# temp-sensor.net
KiCad netlist of a schematic drawn in EAGLE
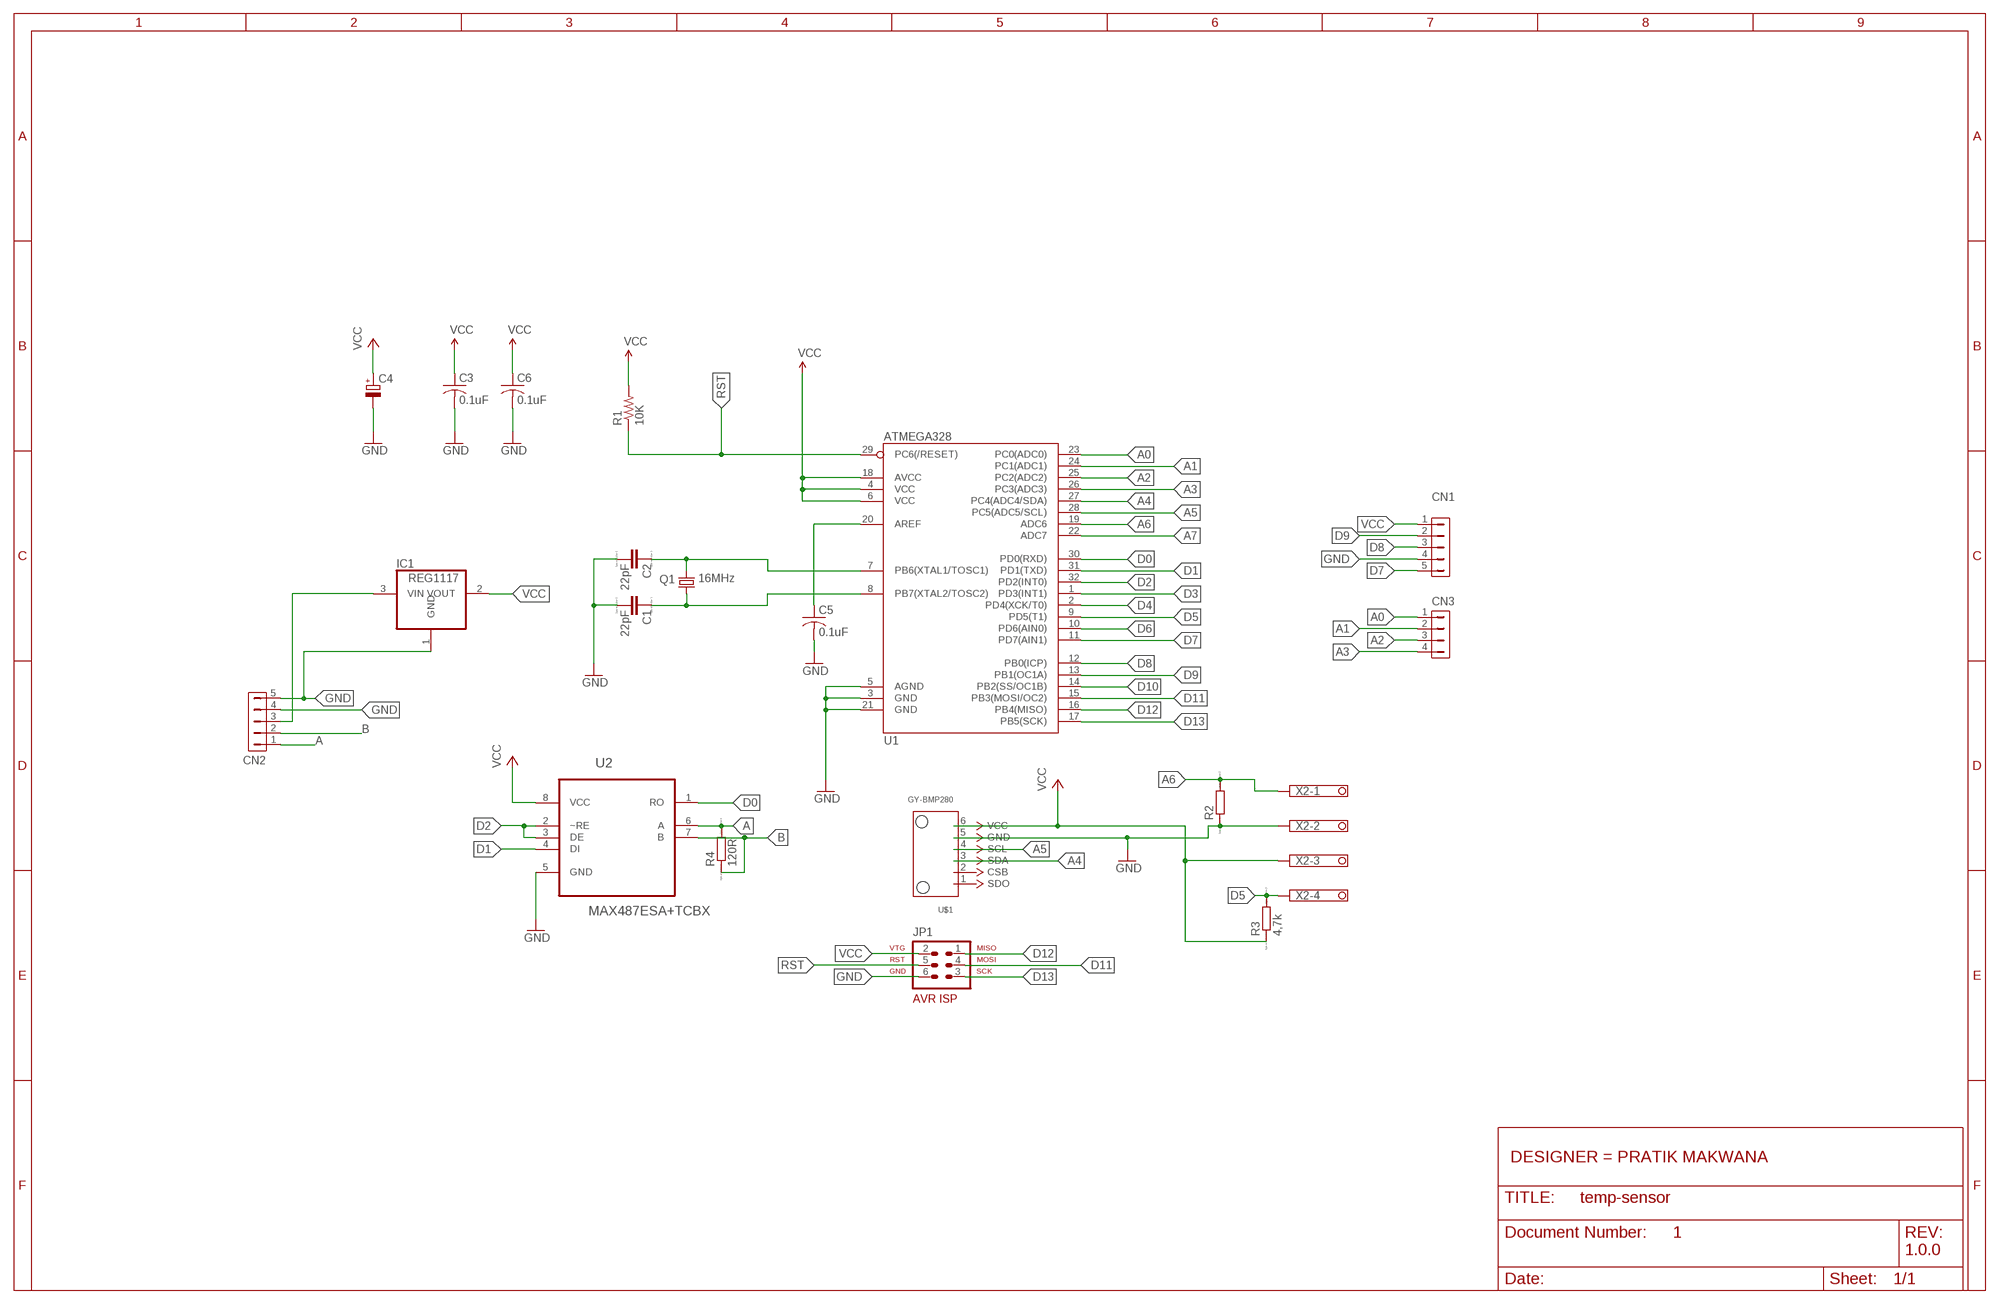
[diagram p0: schematic, sheet 1]

(export (version "E")
  (design (tool "Eeschema 10.0.6"))
  (components
    (comp (ref "C1")
      (value "22pF")
      (footprint "eagle-import:C0805")
      (libsource (lib "eagle-import") (part "C"))
    )
    (comp (ref "C2")
      (value "22pF")
      (footprint "eagle-import:C0805")
      (libsource (lib "eagle-import") (part "C"))
    )
    (comp (ref "C3")
      (value "0.1uF")
      (footprint "eagle-import:C0805")
      (libsource (lib "eagle-import") (part "C-USC0805"))
    )
    (comp (ref "C4")
      (value "CPOL-EUSANYO_SMD_C6")
      (footprint "eagle-import:SANYO-OSCON_SMD_C6")
      (libsource (lib "eagle-import") (part "CPOL-EUSANYO_SMD_C6"))
    )
    (comp (ref "C5")
      (value "0.1uF")
      (footprint "eagle-import:C0805")
      (libsource (lib "eagle-import") (part "C-USC0805"))
    )
    (comp (ref "C6")
      (value "0.1uF")
      (footprint "eagle-import:C0805")
      (libsource (lib "eagle-import") (part "C-USC0805"))
    )
    (comp (ref "CN1")
      (value "HDR-1X5-SIP-100")
      (footprint "eagle-import:SIP-100-5V")
      (libsource (lib "eagle-import") (part "HDR-1X5-SIP-100"))
    )
    (comp (ref "CN2")
      (value "HDR-1X5-SIP-100")
      (footprint "eagle-import:SIP-100-5V")
      (libsource (lib "eagle-import") (part "HDR-1X5-SIP-100"))
    )
    (comp (ref "CN3")
      (value "HDR-1X4-SIP-100")
      (footprint "eagle-import:SIP-100-4V")
      (libsource (lib "eagle-import") (part "HDR-1X4-SIP-100"))
    )
    (comp (ref "IC1")
      (value "REG1117")
      (footprint "eagle-import:SOT223")
      (libsource (lib "eagle-import") (part "REG1117"))
    )
    (comp (ref "JP1")
      (value "AVR-ISP-6")
      (footprint "eagle-import:AVR-ISP-6")
      (libsource (lib "eagle-import") (part "AVR-ISP-6"))
    )
    (comp (ref "Q1")
      (value "16MHz")
      (footprint "eagle-import:HC49_S")
      (libsource (lib "eagle-import") (part "CRYTALHC49S"))
    )
    (comp (ref "R1")
      (value "10K")
      (footprint "eagle-import:R1206")
      (libsource (lib "eagle-import") (part "R-US_R1206"))
    )
    (comp (ref "R2")
      (value "RR1206")
      (footprint "eagle-import:R1206")
      (libsource (lib "eagle-import") (part "RR1206"))
    )
    (comp (ref "R3")
      (value "4,7k")
      (footprint "eagle-import:R1206")
      (libsource (lib "eagle-import") (part "RR1206"))
    )
    (comp (ref "R4")
      (value "120R")
      (footprint "eagle-import:R0603")
      (libsource (lib "eagle-import") (part "RR0603"))
    )
    (comp (ref "U$1")
      (value "GY-BMP280")
      (footprint "eagle-import:GY-BMP280")
      (libsource (lib "eagle-import") (part "GY-BMP280"))
    )
    (comp (ref "U1")
      (value "ATMEGA328")
      (footprint "eagle-import:TQFP32-08")
      (libsource (lib "eagle-import") (part "ATMEGA328"))
    )
    (comp (ref "U2")
      (value "MAX487ESA+TCBX")
      (footprint "eagle-import:SOIC127P600X175-8N")
      (fields (field (name "MF") "Maxim Integrated"))
      (libsource (lib "eagle-import") (part "MAX487ESA+TCBX"))
    )
    (comp (ref "X2")
      (value "TERMINAL-BLOCK-3.5MM-4-PIN-LONG-PAD")
      (footprint "eagle-import:TERMINAL-BLOCK-4-PIN-3.5MM-LONG-PAD")
      (libsource (lib "eagle-import") (part "TERMINAL-BLOCK-3.5MM-4-PIN-LONG-PAD"))
    )
  )
  (nets
    (net (code "1") (name "A") (class "Default")
      (node (ref "CN2") (pin "1") (pinfunction "1_1") (pintype "passive"))
      (node (ref "R4") (pin "2") (pinfunction "2_2") (pintype "passive"))
      (node (ref "U2") (pin "6") (pinfunction "A_6") (pintype "bidirectional"))
    )
    (net (code "2") (name "A0") (class "Default")
      (node (ref "CN3") (pin "1") (pinfunction "1_1") (pintype "passive"))
      (node (ref "U1") (pin "23") (pinfunction "PC0(ADC0)_23") (pintype "bidirectional"))
    )
    (net (code "3") (name "A1") (class "Default")
      (node (ref "CN3") (pin "2") (pinfunction "2_2") (pintype "passive"))
      (node (ref "U1") (pin "24") (pinfunction "PC1(ADC1)_24") (pintype "bidirectional"))
    )
    (net (code "4") (name "A2") (class "Default")
      (node (ref "CN3") (pin "3") (pinfunction "3_3") (pintype "passive"))
      (node (ref "U1") (pin "25") (pinfunction "PC2(ADC2)_25") (pintype "bidirectional"))
    )
    (net (code "5") (name "A3") (class "Default")
      (node (ref "CN3") (pin "4") (pinfunction "4_4") (pintype "passive"))
      (node (ref "U1") (pin "26") (pinfunction "PC3(ADC3)_26") (pintype "bidirectional"))
    )
    (net (code "6") (name "A4") (class "Default")
      (node (ref "U$1") (pin "3") (pinfunction "SDA_3") (pintype "bidirectional"))
      (node (ref "U1") (pin "27") (pinfunction "PC4(ADC4/SDA)_27") (pintype "bidirectional"))
    )
    (net (code "7") (name "A5") (class "Default")
      (node (ref "U$1") (pin "4") (pinfunction "SCL_4") (pintype "bidirectional"))
      (node (ref "U1") (pin "28") (pinfunction "PC5(ADC5/SCL)_28") (pintype "bidirectional"))
    )
    (net (code "8") (name "A6") (class "Default")
      (node (ref "R2") (pin "2") (pinfunction "2_2") (pintype "passive"))
      (node (ref "U1") (pin "19") (pinfunction "ADC6_19") (pintype "bidirectional"))
      (node (ref "X2") (pin "1") (pinfunction "K_1") (pintype "passive"))
    )
    (net (code "9") (name "A7") (class "Default")
      (node (ref "U1") (pin "22") (pinfunction "ADC7_22") (pintype "bidirectional"))
    )
    (net (code "10") (name "B") (class "Default")
      (node (ref "CN2") (pin "2") (pinfunction "2_2") (pintype "passive"))
      (node (ref "R4") (pin "1") (pinfunction "1_1") (pintype "passive"))
      (node (ref "U2") (pin "7") (pinfunction "B_7") (pintype "bidirectional"))
    )
    (net (code "11") (name "D0") (class "Default")
      (node (ref "U1") (pin "30") (pinfunction "PD0(RXD)_30") (pintype "bidirectional"))
      (node (ref "U2") (pin "1") (pinfunction "RO_1") (pintype "output"))
    )
    (net (code "12") (name "D1") (class "Default")
      (node (ref "U1") (pin "31") (pinfunction "PD1(TXD)_31") (pintype "bidirectional"))
      (node (ref "U2") (pin "4") (pinfunction "DI_4") (pintype "input"))
    )
    (net (code "13") (name "D2") (class "Default")
      (node (ref "U1") (pin "32") (pinfunction "PD2(INT0)_32") (pintype "bidirectional"))
      (node (ref "U2") (pin "2") (pinfunction "~{RE}_2") (pintype "input"))
      (node (ref "U2") (pin "3") (pinfunction "DE_3") (pintype "input"))
    )
    (net (code "14") (name "D3") (class "Default")
      (node (ref "U1") (pin "1") (pinfunction "PD3(INT1)_1") (pintype "bidirectional"))
    )
    (net (code "15") (name "D4") (class "Default")
      (node (ref "U1") (pin "2") (pinfunction "PD4(XCK/T0)_2") (pintype "bidirectional"))
    )
    (net (code "16") (name "D5") (class "Default")
      (node (ref "R3") (pin "2") (pinfunction "2_2") (pintype "passive"))
      (node (ref "U1") (pin "9") (pinfunction "PD5(T1)_9") (pintype "bidirectional"))
      (node (ref "X2") (pin "4") (pinfunction "K_4") (pintype "passive"))
    )
    (net (code "17") (name "D6") (class "Default")
      (node (ref "U1") (pin "10") (pinfunction "PD6(AIN0)_10") (pintype "bidirectional"))
    )
    (net (code "18") (name "D7") (class "Default")
      (node (ref "CN1") (pin "5") (pinfunction "5_5") (pintype "passive"))
      (node (ref "U1") (pin "11") (pinfunction "PD7(AIN1)_11") (pintype "bidirectional"))
    )
    (net (code "19") (name "D8") (class "Default")
      (node (ref "CN1") (pin "3") (pinfunction "3_3") (pintype "passive"))
      (node (ref "U1") (pin "12") (pinfunction "PB0(ICP)_12") (pintype "bidirectional"))
    )
    (net (code "20") (name "D9") (class "Default")
      (node (ref "CN1") (pin "2") (pinfunction "2_2") (pintype "passive"))
      (node (ref "U1") (pin "13") (pinfunction "PB1(OC1A)_13") (pintype "bidirectional"))
    )
    (net (code "21") (name "D10") (class "Default")
      (node (ref "U1") (pin "14") (pinfunction "PB2(SS/OC1B)_14") (pintype "bidirectional"))
    )
    (net (code "22") (name "D11") (class "Default")
      (node (ref "JP1") (pin "4") (pinfunction "4_4") (pintype "passive"))
      (node (ref "U1") (pin "15") (pinfunction "PB3(MOSI/OC2)_15") (pintype "bidirectional"))
    )
    (net (code "23") (name "D12") (class "Default")
      (node (ref "JP1") (pin "1") (pinfunction "1_1") (pintype "passive"))
      (node (ref "U1") (pin "16") (pinfunction "PB4(MISO)_16") (pintype "bidirectional"))
    )
    (net (code "24") (name "D13") (class "Default")
      (node (ref "JP1") (pin "3") (pinfunction "3_3") (pintype "passive"))
      (node (ref "U1") (pin "17") (pinfunction "PB5(SCK)_17") (pintype "bidirectional"))
    )
    (net (code "25") (name "GND") (class "Default")
      (node (ref "C1") (pin "2") (pinfunction "2_2") (pintype "passive"))
      (node (ref "C2") (pin "2") (pinfunction "2_2") (pintype "passive"))
      (node (ref "C3") (pin "2") (pinfunction "2_2") (pintype "passive"))
      (node (ref "C4") (pin "-") (pinfunction "-_-") (pintype "passive"))
      (node (ref "C5") (pin "2") (pinfunction "2_2") (pintype "passive"))
      (node (ref "C6") (pin "2") (pinfunction "2_2") (pintype "passive"))
      (node (ref "CN1") (pin "4") (pinfunction "4_4") (pintype "passive"))
      (node (ref "CN2") (pin "4") (pinfunction "4_4") (pintype "passive"))
      (node (ref "CN2") (pin "5") (pinfunction "5_5") (pintype "passive"))
      (node (ref "IC1") (pin "1") (pinfunction "GND_1") (pintype "power_in"))
      (node (ref "JP1") (pin "6") (pinfunction "6_6") (pintype "passive"))
      (node (ref "R2") (pin "1") (pinfunction "1_1") (pintype "passive"))
      (node (ref "U$1") (pin "5") (pinfunction "GND_5") (pintype "bidirectional"))
      (node (ref "U1") (pin "21") (pinfunction "GND_21") (pintype "bidirectional"))
      (node (ref "U1") (pin "3") (pinfunction "GND_3") (pintype "bidirectional"))
      (node (ref "U1") (pin "5") (pinfunction "AGND_5") (pintype "bidirectional"))
      (node (ref "U2") (pin "5") (pinfunction "GND_5") (pintype "passive"))
      (node (ref "X2") (pin "2") (pinfunction "K_2") (pintype "passive"))
    )
    (net (code "26") (name "Net-(IC1-VIN)") (class "Default")
      (node (ref "CN2") (pin "3") (pinfunction "3_3") (pintype "passive"))
      (node (ref "IC1") (pin "3") (pinfunction "VIN_3") (pintype "input"))
    )
    (net (code "27") (name "Net-(U1-AREF)") (class "Default")
      (node (ref "C5") (pin "1") (pinfunction "1_1") (pintype "passive"))
      (node (ref "U1") (pin "20") (pinfunction "AREF_20") (pintype "bidirectional"))
    )
    (net (code "28") (name "Net-(U1-PB6(XTAL1{slash}TOSC1))") (class "Default")
      (node (ref "C2") (pin "1") (pinfunction "1_1") (pintype "passive"))
      (node (ref "Q1") (pin "2") (pinfunction "2_2") (pintype "passive"))
      (node (ref "U1") (pin "7") (pinfunction "PB6(XTAL1/TOSC1)_7") (pintype "bidirectional"))
    )
    (net (code "29") (name "Net-(U1-PB7(XTAL2{slash}TOSC2))") (class "Default")
      (node (ref "C1") (pin "1") (pinfunction "1_1") (pintype "passive"))
      (node (ref "Q1") (pin "1") (pinfunction "1_1") (pintype "passive"))
      (node (ref "U1") (pin "8") (pinfunction "PB7(XTAL2/TOSC2)_8") (pintype "bidirectional"))
    )
    (net (code "30") (name "RST") (class "Default")
      (node (ref "JP1") (pin "5") (pinfunction "5_5") (pintype "passive"))
      (node (ref "R1") (pin "1") (pinfunction "1_1") (pintype "passive"))
      (node (ref "U1") (pin "29") (pinfunction "PC6(/RESET)_29") (pintype "bidirectional"))
    )
    (net (code "31") (name "VCC") (class "Default")
      (node (ref "C3") (pin "1") (pinfunction "1_1") (pintype "passive"))
      (node (ref "C4") (pin "+") (pinfunction "+_+") (pintype "passive"))
      (node (ref "C6") (pin "1") (pinfunction "1_1") (pintype "passive"))
      (node (ref "CN1") (pin "1") (pinfunction "1_1") (pintype "passive"))
      (node (ref "IC1") (pin "2") (pinfunction "VOUT_2") (pintype "output"))
      (node (ref "JP1") (pin "2") (pinfunction "2_2") (pintype "passive"))
      (node (ref "R1") (pin "2") (pinfunction "2_2") (pintype "passive"))
      (node (ref "R3") (pin "1") (pinfunction "1_1") (pintype "passive"))
      (node (ref "U$1") (pin "6") (pinfunction "VCC_6") (pintype "power_in"))
      (node (ref "U1") (pin "18") (pinfunction "AVCC_18") (pintype "bidirectional"))
      (node (ref "U1") (pin "4") (pinfunction "VCC_4") (pintype "bidirectional"))
      (node (ref "U1") (pin "6") (pinfunction "VCC_6") (pintype "bidirectional"))
      (node (ref "U2") (pin "8") (pinfunction "VCC_8") (pintype "power_in"))
      (node (ref "X2") (pin "3") (pinfunction "K_3") (pintype "passive"))
    )
    (net (code "32") (name "unconnected-(U$1-CSB-Pad2)") (class "Default")
      (node (ref "U$1") (pin "2") (pinfunction "CSB_2") (pintype "bidirectional"))
    )
    (net (code "33") (name "unconnected-(U$1-SDO-Pad1)") (class "Default")
      (node (ref "U$1") (pin "1") (pinfunction "SDO_1") (pintype "bidirectional"))
    )
  )
)
